# ctrl.net
KiCad netlist of a schematic drawn in EAGLE
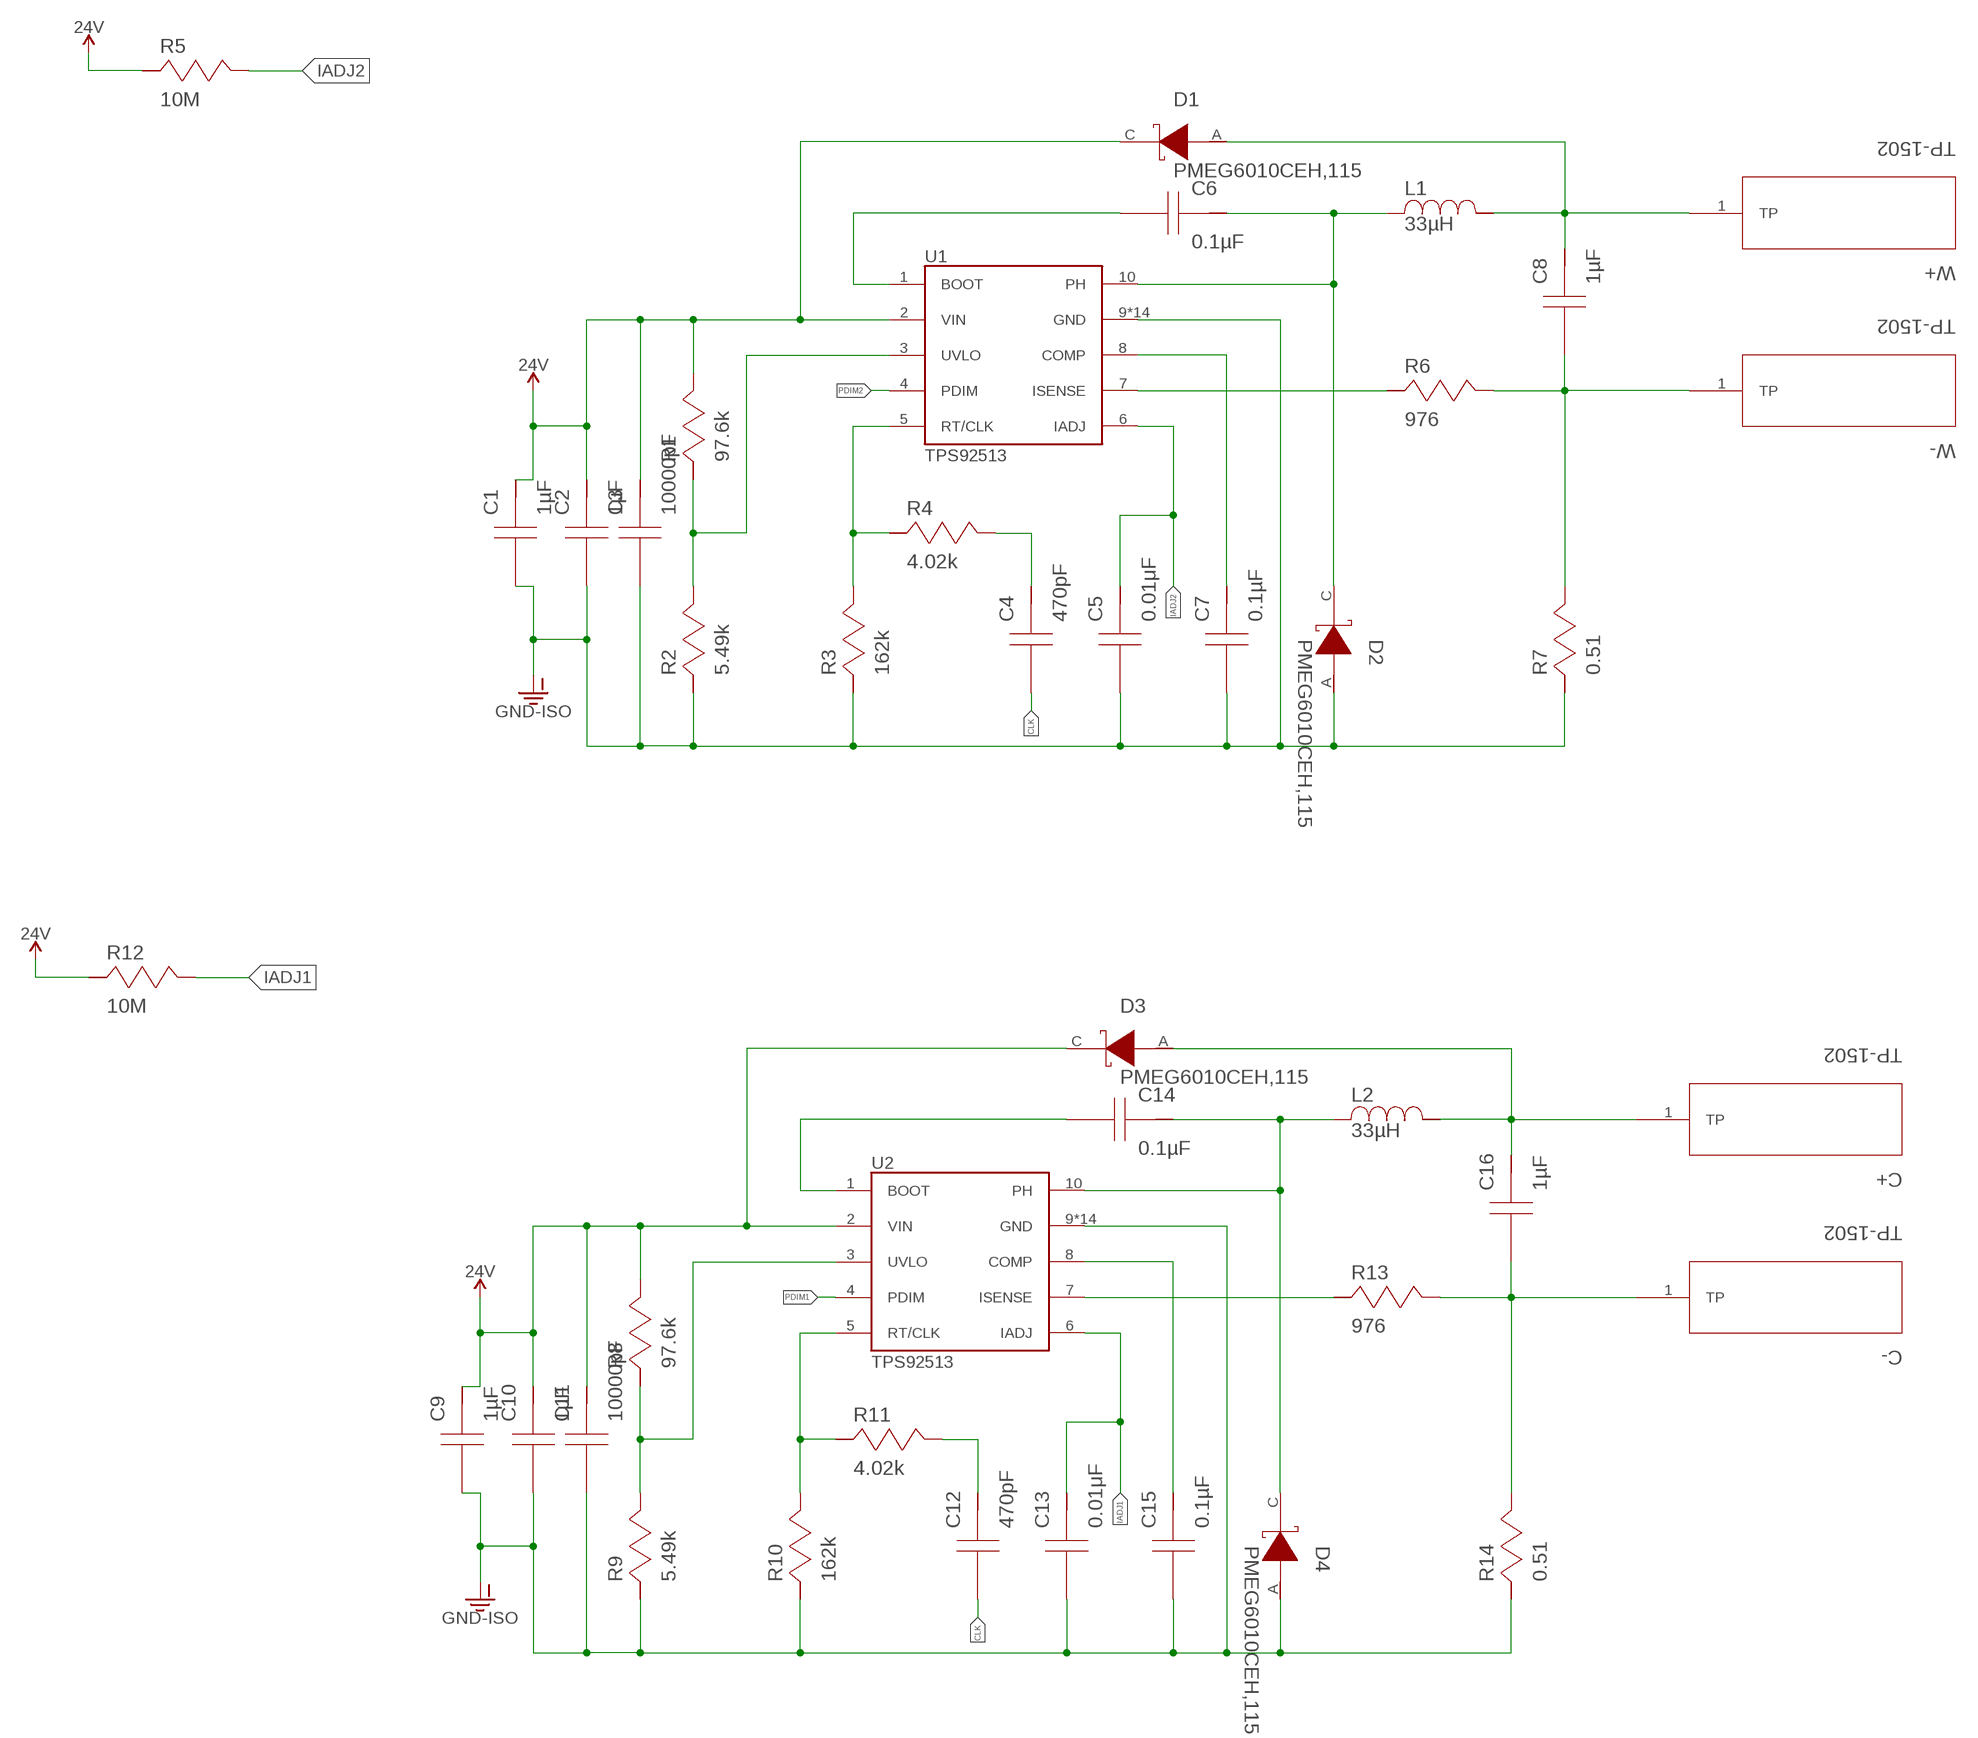
[diagram p0: schematic, sheet 1, part 1 of 2]
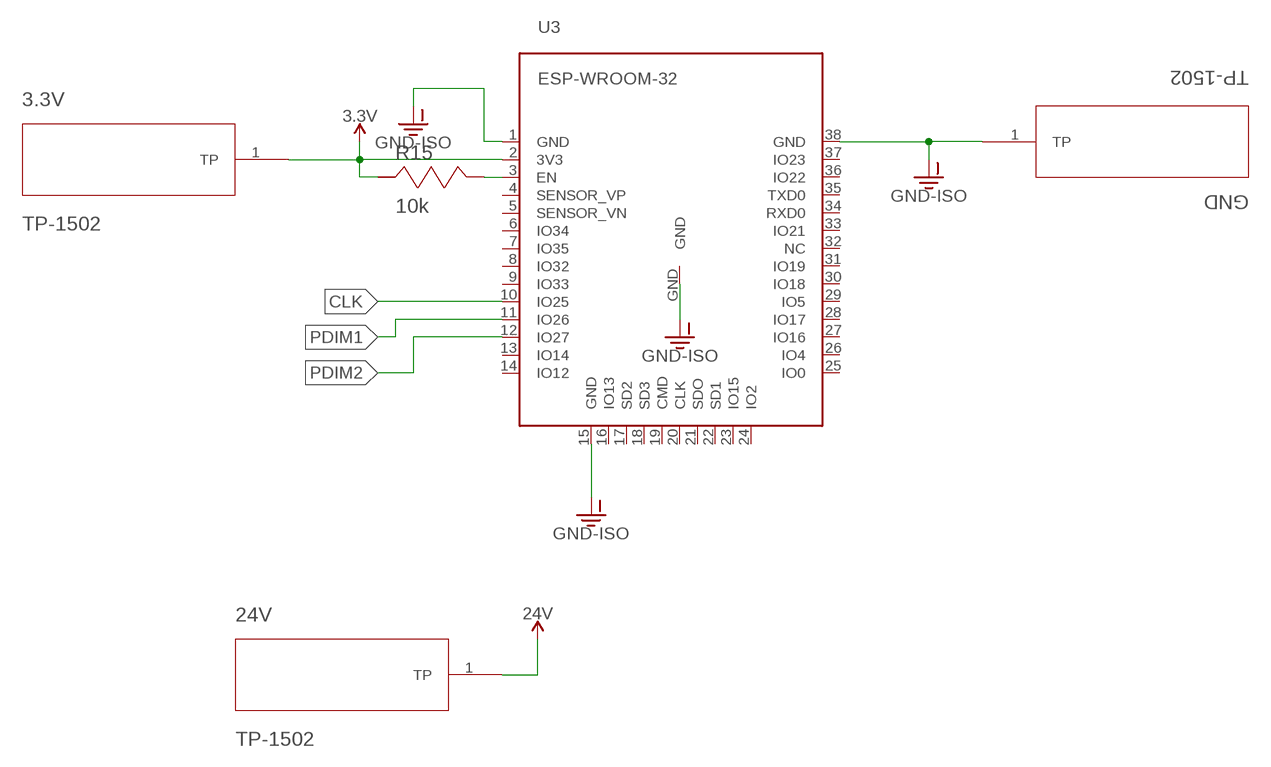
[diagram p1: schematic, sheet 1, part 2 of 2]

(export (version "E")
  (design (tool "Eeschema 10.0.6"))
  (components
    (comp (ref "3.3V")
      (value "TP-1502")
      (footprint "eagle-import:TP-1502")
      (libsource (lib "eagle-import") (part "TP-1502"))
    )
    (comp (ref "24V")
      (value "TP-1502")
      (footprint "eagle-import:TP-1502")
      (libsource (lib "eagle-import") (part "TP-1502"))
    )
    (comp (ref "C+")
      (value "TP-1502")
      (footprint "eagle-import:TP-1502")
      (libsource (lib "eagle-import") (part "TP-1502"))
    )
    (comp (ref "C-")
      (value "TP-1502")
      (footprint "eagle-import:TP-1502")
      (libsource (lib "eagle-import") (part "TP-1502"))
    )
    (comp (ref "C1")
      (value "1µF")
      (footprint "eagle-import:1206")
      (fields
        (field (name "DIGIKEY_PART_NUMBER") "490-6527-1-ND")
        (field (name "PART_NUMBER") "GRM31MR71H105KA88L")
      )
      (libsource (lib "eagle-import") (part "GRM31MR71H105KA88L"))
    )
    (comp (ref "C2")
      (value "1µF")
      (footprint "eagle-import:1206")
      (fields
        (field (name "DIGIKEY_PART_NUMBER") "490-6527-1-ND")
        (field (name "PART_NUMBER") "GRM31MR71H105KA88L")
      )
      (libsource (lib "eagle-import") (part "GRM31MR71H105KA88L"))
    )
    (comp (ref "C3")
      (value "10000pF")
      (footprint "eagle-import:0402")
      (fields
        (field (name "DIGIKEY_PART_NUMBER") "490-4762-1-ND ")
        (field (name "PART_NUMBER") "GCM155R71H103KA55D")
      )
      (libsource (lib "eagle-import") (part "GCM155R71H103KA55D"))
    )
    (comp (ref "C4")
      (value "470pF")
      (footprint "eagle-import:0603")
      (fields
        (field (name "DIGIKEY_PART_NUMBER") "399-5338-1-ND")
        (field (name "MANUFACTURER") "KEMET")
        (field (name "PART_NUMBER") "C0603X471K5RACTU")
      )
      (libsource (lib "eagle-import") (part "C0603X471K5RACTU"))
    )
    (comp (ref "C5")
      (value "0.01μF")
      (footprint "eagle-import:0805")
      (fields
        (field (name "DIGIKEY_PART_NUMBER") "311-1136-1-ND")
        (field (name "PART_NUMBER") "CC0805KRX7R9BB103")
      )
      (libsource (lib "eagle-import") (part "CC0805KRX7R9BB103"))
    )
    (comp (ref "C6")
      (value "0.1µF")
      (footprint "eagle-import:0603")
      (fields
        (field (name "DIGIKEY_PART_NUMBER") "490-1524-1-ND")
        (field (name "MANUFACTURER") "Murata Electronics North America")
        (field (name "PART_NUMBER") "GRM188R71E104KA01D")
      )
      (libsource (lib "eagle-import") (part "GRM188R71E104KA01D"))
    )
    (comp (ref "C7")
      (value "0.1µF")
      (footprint "eagle-import:0805")
      (fields
        (field (name "DIGIKEY_PART_NUMBER") "311-1141-1-ND")
        (field (name "PART_NUMBER") "CC0805KRX7R8BB104")
      )
      (libsource (lib "eagle-import") (part "CC0805KRX7R8BB104"))
    )
    (comp (ref "C8")
      (value "1µF")
      (footprint "eagle-import:0805")
      (fields
        (field (name "DIGIKEY_PART_NUMBER") "587-1438-1-ND")
        (field (name "PART_NUMBER") "GMK212B7105KG-T")
      )
      (libsource (lib "eagle-import") (part "GMK212B7105KG-T"))
    )
    (comp (ref "C9")
      (value "1µF")
      (footprint "eagle-import:1206")
      (fields
        (field (name "DIGIKEY_PART_NUMBER") "490-6527-1-ND")
        (field (name "PART_NUMBER") "GRM31MR71H105KA88L")
      )
      (libsource (lib "eagle-import") (part "GRM31MR71H105KA88L"))
    )
    (comp (ref "C10")
      (value "1µF")
      (footprint "eagle-import:1206")
      (fields
        (field (name "DIGIKEY_PART_NUMBER") "490-6527-1-ND")
        (field (name "PART_NUMBER") "GRM31MR71H105KA88L")
      )
      (libsource (lib "eagle-import") (part "GRM31MR71H105KA88L"))
    )
    (comp (ref "C11")
      (value "10000pF")
      (footprint "eagle-import:0402")
      (fields
        (field (name "DIGIKEY_PART_NUMBER") "490-4762-1-ND ")
        (field (name "PART_NUMBER") "GCM155R71H103KA55D")
      )
      (libsource (lib "eagle-import") (part "GCM155R71H103KA55D"))
    )
    (comp (ref "C12")
      (value "470pF")
      (footprint "eagle-import:0603")
      (fields
        (field (name "DIGIKEY_PART_NUMBER") "399-5338-1-ND")
        (field (name "MANUFACTURER") "KEMET")
        (field (name "PART_NUMBER") "C0603X471K5RACTU")
      )
      (libsource (lib "eagle-import") (part "C0603X471K5RACTU"))
    )
    (comp (ref "C13")
      (value "0.01μF")
      (footprint "eagle-import:0805")
      (fields
        (field (name "DIGIKEY_PART_NUMBER") "311-1136-1-ND")
        (field (name "PART_NUMBER") "CC0805KRX7R9BB103")
      )
      (libsource (lib "eagle-import") (part "CC0805KRX7R9BB103"))
    )
    (comp (ref "C14")
      (value "0.1µF")
      (footprint "eagle-import:0603")
      (fields
        (field (name "DIGIKEY_PART_NUMBER") "490-1524-1-ND")
        (field (name "MANUFACTURER") "Murata Electronics North America")
        (field (name "PART_NUMBER") "GRM188R71E104KA01D")
      )
      (libsource (lib "eagle-import") (part "GRM188R71E104KA01D"))
    )
    (comp (ref "C15")
      (value "0.1µF")
      (footprint "eagle-import:0805")
      (fields
        (field (name "DIGIKEY_PART_NUMBER") "311-1141-1-ND")
        (field (name "PART_NUMBER") "CC0805KRX7R8BB104")
      )
      (libsource (lib "eagle-import") (part "CC0805KRX7R8BB104"))
    )
    (comp (ref "C16")
      (value "1µF")
      (footprint "eagle-import:0805")
      (fields
        (field (name "DIGIKEY_PART_NUMBER") "587-1438-1-ND")
        (field (name "PART_NUMBER") "GMK212B7105KG-T")
      )
      (libsource (lib "eagle-import") (part "GMK212B7105KG-T"))
    )
    (comp (ref "D1")
      (value "PMEG6010CEH,115")
      (footprint "eagle-import:SOD-123F")
      (fields (field (name "DIGIKEY_PART_NUMBER") "1727-3848-1-ND"))
      (libsource (lib "eagle-import") (part "PMEG6010CEH,115"))
    )
    (comp (ref "D2")
      (value "PMEG6010CEH,115")
      (footprint "eagle-import:SOD-123F")
      (fields (field (name "DIGIKEY_PART_NUMBER") "1727-3848-1-ND"))
      (libsource (lib "eagle-import") (part "PMEG6010CEH,115"))
    )
    (comp (ref "D3")
      (value "PMEG6010CEH,115")
      (footprint "eagle-import:SOD-123F")
      (fields (field (name "DIGIKEY_PART_NUMBER") "1727-3848-1-ND"))
      (libsource (lib "eagle-import") (part "PMEG6010CEH,115"))
    )
    (comp (ref "D4")
      (value "PMEG6010CEH,115")
      (footprint "eagle-import:SOD-123F")
      (fields (field (name "DIGIKEY_PART_NUMBER") "1727-3848-1-ND"))
      (libsource (lib "eagle-import") (part "PMEG6010CEH,115"))
    )
    (comp (ref "GND")
      (value "TP-1502")
      (footprint "eagle-import:TP-1502")
      (libsource (lib "eagle-import") (part "TP-1502"))
    )
    (comp (ref "L1")
      (value "33µH")
      (footprint "eagle-import:SRN6045")
      (fields
        (field (name "DIGIKEY_PART_NUMBER") "SRN6045-330MCT-ND")
        (field (name "PART_NUMBER") "SRN6045-330M")
      )
      (libsource (lib "eagle-import") (part "SRN6045-330M"))
    )
    (comp (ref "L2")
      (value "33µH")
      (footprint "eagle-import:SRN6045")
      (fields
        (field (name "DIGIKEY_PART_NUMBER") "SRN6045-330MCT-ND")
        (field (name "PART_NUMBER") "SRN6045-330M")
      )
      (libsource (lib "eagle-import") (part "SRN6045-330M"))
    )
    (comp (ref "R1")
      (value "97.6k")
      (footprint "eagle-import:0402")
      (fields
        (field (name "DIGIKEY_PART_NUMBER") "541-97.6KLCT-ND")
        (field (name "PART_NUMBER") "CRCW040297K6FKED")
      )
      (libsource (lib "eagle-import") (part "CRCW040297K6FKED"))
    )
    (comp (ref "R2")
      (value "5.49k")
      (footprint "eagle-import:0402")
      (fields
        (field (name "DIGIKEY_PART_NUMBER") "541-5.49KLCT-ND")
        (field (name "PART_NUMBER") "CRCW04025K49FKED")
      )
      (libsource (lib "eagle-import") (part "CRCW04025K49FKED"))
    )
    (comp (ref "R3")
      (value "162k")
      (footprint "eagle-import:0402")
      (fields
        (field (name "DIGIKEY_PART_NUMBER") "541-162KLCT-ND")
        (field (name "PART_NUMBER") "CRCW0402162KFKED")
      )
      (libsource (lib "eagle-import") (part "CRCW0402162KFKED"))
    )
    (comp (ref "R4")
      (value "4.02k")
      (footprint "eagle-import:0603")
      (fields
        (field (name "DIGIKEY_PART_NUMBER") "541-4.02KHCT-ND")
        (field (name "MANUFACTURER") "Vishay Dale")
        (field (name "PART_NUMBER") "CRCW06034K02FKEA")
      )
      (libsource (lib "eagle-import") (part "CRCW06034K02FKEA"))
    )
    (comp (ref "R5")
      (value "10M")
      (footprint "eagle-import:0402")
      (fields
        (field (name "DIGIKEY_PART_NUMBER") "541-10MJCT-ND")
        (field (name "MANUFACTURER") "Vishay Dale")
        (field (name "PART_NUMBER") "CRCW040210M0JNED")
      )
      (libsource (lib "eagle-import") (part "CRCW040210M0JNED"))
    )
    (comp (ref "R6")
      (value "976")
      (footprint "eagle-import:0402")
      (fields
        (field (name "DIGIKEY_PART_NUMBER") "541-976LCT-ND")
        (field (name "PART_NUMBER") "CRCW0402976RFKED")
      )
      (libsource (lib "eagle-import") (part "CRCW0402976RFKED"))
    )
    (comp (ref "R7")
      (value "0.51")
      (footprint "eagle-import:0805")
      (fields
        (field (name "DIGIKEY_PART_NUMBER") "CRM0805-FX-R510ELFCT-ND")
        (field (name "PART_NUMBER") "CRM0805-FX-R510ELF")
      )
      (libsource (lib "eagle-import") (part "CRM0805-FX-R510ELF"))
    )
    (comp (ref "R8")
      (value "97.6k")
      (footprint "eagle-import:0402")
      (fields
        (field (name "DIGIKEY_PART_NUMBER") "541-97.6KLCT-ND")
        (field (name "PART_NUMBER") "CRCW040297K6FKED")
      )
      (libsource (lib "eagle-import") (part "CRCW040297K6FKED"))
    )
    (comp (ref "R9")
      (value "5.49k")
      (footprint "eagle-import:0402")
      (fields
        (field (name "DIGIKEY_PART_NUMBER") "541-5.49KLCT-ND")
        (field (name "PART_NUMBER") "CRCW04025K49FKED")
      )
      (libsource (lib "eagle-import") (part "CRCW04025K49FKED"))
    )
    (comp (ref "R10")
      (value "162k")
      (footprint "eagle-import:0402")
      (fields
        (field (name "DIGIKEY_PART_NUMBER") "541-162KLCT-ND")
        (field (name "PART_NUMBER") "CRCW0402162KFKED")
      )
      (libsource (lib "eagle-import") (part "CRCW0402162KFKED"))
    )
    (comp (ref "R11")
      (value "4.02k")
      (footprint "eagle-import:0603")
      (fields
        (field (name "DIGIKEY_PART_NUMBER") "541-4.02KHCT-ND")
        (field (name "MANUFACTURER") "Vishay Dale")
        (field (name "PART_NUMBER") "CRCW06034K02FKEA")
      )
      (libsource (lib "eagle-import") (part "CRCW06034K02FKEA"))
    )
    (comp (ref "R12")
      (value "10M")
      (footprint "eagle-import:0402")
      (fields
        (field (name "DIGIKEY_PART_NUMBER") "541-10MJCT-ND")
        (field (name "MANUFACTURER") "Vishay Dale")
        (field (name "PART_NUMBER") "CRCW040210M0JNED")
      )
      (libsource (lib "eagle-import") (part "CRCW040210M0JNED"))
    )
    (comp (ref "R13")
      (value "976")
      (footprint "eagle-import:0402")
      (fields
        (field (name "DIGIKEY_PART_NUMBER") "541-976LCT-ND")
        (field (name "PART_NUMBER") "CRCW0402976RFKED")
      )
      (libsource (lib "eagle-import") (part "CRCW0402976RFKED"))
    )
    (comp (ref "R14")
      (value "0.51")
      (footprint "eagle-import:0805")
      (fields
        (field (name "DIGIKEY_PART_NUMBER") "CRM0805-FX-R510ELFCT-ND")
        (field (name "PART_NUMBER") "CRM0805-FX-R510ELF")
      )
      (libsource (lib "eagle-import") (part "CRM0805-FX-R510ELF"))
    )
    (comp (ref "R15")
      (value "10k")
      (footprint "eagle-import:0603")
      (fields
        (field (name "DIGIKEY_PART_NUMBER") "541-10.0KHCT-ND")
        (field (name "MANUFACTURER") "Vishay Dale")
        (field (name "PART_NUMBER") "CRCW060310K0FKEA")
      )
      (libsource (lib "eagle-import") (part "CRCW060310K0FKEA"))
    )
    (comp (ref "U1")
      (value "TPS92513")
      (footprint "eagle-import:TPS92513")
      (fields
        (field (name "DIGIKEY_PART_NUMBER") "296-42113-1-ND")
        (field (name "PART_NUMBER") "TPS92513DGQT")
      )
      (libsource (lib "eagle-import") (part "TPS92513"))
    )
    (comp (ref "U2")
      (value "TPS92513")
      (footprint "eagle-import:TPS92513")
      (fields
        (field (name "DIGIKEY_PART_NUMBER") "296-42113-1-ND")
        (field (name "PART_NUMBER") "TPS92513DGQT")
      )
      (libsource (lib "eagle-import") (part "TPS92513"))
    )
    (comp (ref "U3")
      (value "ESP-WROOM-32")
      (footprint "eagle-import:ESP-WROOM-32")
      (libsource (lib "eagle-import") (part "ESP-WROOM-32"))
    )
    (comp (ref "W+")
      (value "TP-1502")
      (footprint "eagle-import:TP-1502")
      (libsource (lib "eagle-import") (part "TP-1502"))
    )
    (comp (ref "W-")
      (value "TP-1502")
      (footprint "eagle-import:TP-1502")
      (libsource (lib "eagle-import") (part "TP-1502"))
    )
  )
  (nets
    (net (code "1") (name "3.3V") (class "Default")
      (node (ref "3.3V") (pin "1") (pinfunction "TP_1") (pintype "passive"))
      (node (ref "R15") (pin "2") (pinfunction "2_2") (pintype "passive"))
      (node (ref "U3") (pin "2") (pinfunction "3V3_2") (pintype "bidirectional"))
    )
    (net (code "2") (name "24V") (class "Default")
      (node (ref "24V") (pin "1") (pinfunction "TP_1") (pintype "passive"))
      (node (ref "C1") (pin "1") (pinfunction "1_1") (pintype "passive"))
      (node (ref "C10") (pin "1") (pinfunction "1_1") (pintype "passive"))
      (node (ref "C11") (pin "1") (pinfunction "1_1") (pintype "passive"))
      (node (ref "C2") (pin "1") (pinfunction "1_1") (pintype "passive"))
      (node (ref "C3") (pin "1") (pinfunction "1_1") (pintype "passive"))
      (node (ref "C9") (pin "1") (pinfunction "1_1") (pintype "passive"))
      (node (ref "D1") (pin "C") (pinfunction "C_C") (pintype "passive"))
      (node (ref "D3") (pin "C") (pinfunction "C_C") (pintype "passive"))
      (node (ref "R1") (pin "1") (pinfunction "1_1") (pintype "passive"))
      (node (ref "R12") (pin "2") (pinfunction "2_2") (pintype "passive"))
      (node (ref "R5") (pin "2") (pinfunction "2_2") (pintype "passive"))
      (node (ref "R8") (pin "1") (pinfunction "1_1") (pintype "passive"))
      (node (ref "U1") (pin "2") (pinfunction "VIN_2") (pintype "power_in"))
      (node (ref "U2") (pin "2") (pinfunction "VIN_2") (pintype "power_in"))
    )
    (net (code "3") (name "CLK") (class "Default")
      (node (ref "C12") (pin "2") (pinfunction "2_2") (pintype "passive"))
      (node (ref "C4") (pin "2") (pinfunction "2_2") (pintype "passive"))
      (node (ref "U3") (pin "10") (pinfunction "IO25_10") (pintype "bidirectional"))
    )
    (net (code "4") (name "GND-ISO") (class "Default")
      (node (ref "C1") (pin "2") (pinfunction "2_2") (pintype "passive"))
      (node (ref "C10") (pin "2") (pinfunction "2_2") (pintype "passive"))
      (node (ref "C11") (pin "2") (pinfunction "2_2") (pintype "passive"))
      (node (ref "C13") (pin "2") (pinfunction "2_2") (pintype "passive"))
      (node (ref "C15") (pin "2") (pinfunction "2_2") (pintype "passive"))
      (node (ref "C2") (pin "2") (pinfunction "2_2") (pintype "passive"))
      (node (ref "C3") (pin "2") (pinfunction "2_2") (pintype "passive"))
      (node (ref "C5") (pin "2") (pinfunction "2_2") (pintype "passive"))
      (node (ref "C7") (pin "2") (pinfunction "2_2") (pintype "passive"))
      (node (ref "C9") (pin "2") (pinfunction "2_2") (pintype "passive"))
      (node (ref "D2") (pin "A") (pinfunction "A_A") (pintype "passive"))
      (node (ref "D4") (pin "A") (pinfunction "A_A") (pintype "passive"))
      (node (ref "GND") (pin "1") (pinfunction "TP_1") (pintype "passive"))
      (node (ref "R10") (pin "2") (pinfunction "2_2") (pintype "passive"))
      (node (ref "R14") (pin "2") (pinfunction "2_2") (pintype "passive"))
      (node (ref "R2") (pin "2") (pinfunction "2_2") (pintype "passive"))
      (node (ref "R3") (pin "2") (pinfunction "2_2") (pintype "passive"))
      (node (ref "R7") (pin "2") (pinfunction "2_2") (pintype "passive"))
      (node (ref "R9") (pin "2") (pinfunction "2_2") (pintype "passive"))
      (node (ref "U1") (pin "9") (pinfunction "GND_9") (pintype "power_in"))
      (node (ref "U1") (pin "GND-ISO") (pinfunction "GND_GND-ISO") (pintype "power_in"))
      (node (ref "U1") (pin "P$1") (pinfunction "GND_P$1") (pintype "power_in"))
      (node (ref "U1") (pin "P$10") (pinfunction "GND_P$10") (pintype "power_in"))
      (node (ref "U1") (pin "P$11") (pinfunction "GND_P$11") (pintype "power_in"))
      (node (ref "U1") (pin "P$12") (pinfunction "GND_P$12") (pintype "power_in"))
      (node (ref "U1") (pin "P$2") (pinfunction "GND_P$2") (pintype "power_in"))
      (node (ref "U1") (pin "P$3") (pinfunction "GND_P$3") (pintype "power_in"))
      (node (ref "U1") (pin "P$4") (pinfunction "GND_P$4") (pintype "power_in"))
      (node (ref "U1") (pin "P$5") (pinfunction "GND_P$5") (pintype "power_in"))
      (node (ref "U1") (pin "P$6") (pinfunction "GND_P$6") (pintype "power_in"))
      (node (ref "U1") (pin "P$7") (pinfunction "GND_P$7") (pintype "power_in"))
      (node (ref "U1") (pin "P$8") (pinfunction "GND_P$8") (pintype "power_in"))
      (node (ref "U1") (pin "P$9") (pinfunction "GND_P$9") (pintype "power_in"))
      (node (ref "U2") (pin "9") (pinfunction "GND_9") (pintype "power_in"))
      (node (ref "U2") (pin "GND-ISO") (pinfunction "GND_GND-ISO") (pintype "power_in"))
      (node (ref "U2") (pin "P$1") (pinfunction "GND_P$1") (pintype "power_in"))
      (node (ref "U2") (pin "P$10") (pinfunction "GND_P$10") (pintype "power_in"))
      (node (ref "U2") (pin "P$11") (pinfunction "GND_P$11") (pintype "power_in"))
      (node (ref "U2") (pin "P$12") (pinfunction "GND_P$12") (pintype "power_in"))
      (node (ref "U2") (pin "P$2") (pinfunction "GND_P$2") (pintype "power_in"))
      (node (ref "U2") (pin "P$3") (pinfunction "GND_P$3") (pintype "power_in"))
      (node (ref "U2") (pin "P$4") (pinfunction "GND_P$4") (pintype "power_in"))
      (node (ref "U2") (pin "P$5") (pinfunction "GND_P$5") (pintype "power_in"))
      (node (ref "U2") (pin "P$6") (pinfunction "GND_P$6") (pintype "power_in"))
      (node (ref "U2") (pin "P$7") (pinfunction "GND_P$7") (pintype "power_in"))
      (node (ref "U2") (pin "P$8") (pinfunction "GND_P$8") (pintype "power_in"))
      (node (ref "U2") (pin "P$9") (pinfunction "GND_P$9") (pintype "power_in"))
      (node (ref "U3") (pin "1") (pinfunction "GND_1") (pintype "bidirectional"))
      (node (ref "U3") (pin "15") (pinfunction "GND_15") (pintype "bidirectional"))
      (node (ref "U3") (pin "38") (pinfunction "GND_38") (pintype "bidirectional"))
      (node (ref "U3") (pin "GND") (pinfunction "GND_GND") (pintype "bidirectional"))
    )
    (net (code "5") (name "IADJ1") (class "Default")
      (node (ref "C13") (pin "1") (pinfunction "1_1") (pintype "passive"))
      (node (ref "R12") (pin "1") (pinfunction "1_1") (pintype "passive"))
      (node (ref "U2") (pin "6") (pinfunction "IADJ_6") (pintype "input"))
    )
    (net (code "6") (name "IADJ2") (class "Default")
      (node (ref "C5") (pin "1") (pinfunction "1_1") (pintype "passive"))
      (node (ref "R5") (pin "1") (pinfunction "1_1") (pintype "passive"))
      (node (ref "U1") (pin "6") (pinfunction "IADJ_6") (pintype "input"))
    )
    (net (code "7") (name "Net-(C+-TP)") (class "Default")
      (node (ref "C+") (pin "1") (pinfunction "TP_1") (pintype "passive"))
      (node (ref "C16") (pin "1") (pinfunction "1_1") (pintype "passive"))
      (node (ref "D3") (pin "A") (pinfunction "A_A") (pintype "passive"))
      (node (ref "L2") (pin "2") (pinfunction "2_2") (pintype "passive"))
    )
    (net (code "8") (name "Net-(C--TP)") (class "Default")
      (node (ref "C-") (pin "1") (pinfunction "TP_1") (pintype "passive"))
      (node (ref "C16") (pin "2") (pinfunction "2_2") (pintype "passive"))
      (node (ref "R13") (pin "1") (pinfunction "1_1") (pintype "passive"))
      (node (ref "R14") (pin "1") (pinfunction "1_1") (pintype "passive"))
    )
    (net (code "9") (name "Net-(C4-Pad1)") (class "Default")
      (node (ref "C4") (pin "1") (pinfunction "1_1") (pintype "passive"))
      (node (ref "R4") (pin "1") (pinfunction "1_1") (pintype "passive"))
    )
    (net (code "10") (name "Net-(C12-Pad1)") (class "Default")
      (node (ref "C12") (pin "1") (pinfunction "1_1") (pintype "passive"))
      (node (ref "R11") (pin "1") (pinfunction "1_1") (pintype "passive"))
    )
    (net (code "11") (name "Net-(U1-BOOT)") (class "Default")
      (node (ref "C6") (pin "2") (pinfunction "2_2") (pintype "passive"))
      (node (ref "U1") (pin "1") (pinfunction "BOOT_1") (pintype "output"))
    )
    (net (code "12") (name "Net-(U1-COMP)") (class "Default")
      (node (ref "C7") (pin "1") (pinfunction "1_1") (pintype "passive"))
      (node (ref "U1") (pin "8") (pinfunction "COMP_8") (pintype "output"))
    )
    (net (code "13") (name "Net-(U1-ISENSE)") (class "Default")
      (node (ref "R6") (pin "2") (pinfunction "2_2") (pintype "passive"))
      (node (ref "U1") (pin "7") (pinfunction "ISENSE_7") (pintype "input"))
    )
    (net (code "14") (name "Net-(U1-PH)") (class "Default")
      (node (ref "C6") (pin "1") (pinfunction "1_1") (pintype "passive"))
      (node (ref "D2") (pin "C") (pinfunction "C_C") (pintype "passive"))
      (node (ref "L1") (pin "1") (pinfunction "1_1") (pintype "passive"))
      (node (ref "U1") (pin "10") (pinfunction "PH_10") (pintype "output"))
    )
    (net (code "15") (name "Net-(U1-RT{slash}CLK)") (class "Default")
      (node (ref "R3") (pin "1") (pinfunction "1_1") (pintype "passive"))
      (node (ref "R4") (pin "2") (pinfunction "2_2") (pintype "passive"))
      (node (ref "U1") (pin "5") (pinfunction "RT/CLK_5") (pintype "input"))
    )
    (net (code "16") (name "Net-(U1-UVLO)") (class "Default")
      (node (ref "R1") (pin "2") (pinfunction "2_2") (pintype "passive"))
      (node (ref "R2") (pin "1") (pinfunction "1_1") (pintype "passive"))
      (node (ref "U1") (pin "3") (pinfunction "UVLO_3") (pintype "input"))
    )
    (net (code "17") (name "Net-(U2-BOOT)") (class "Default")
      (node (ref "C14") (pin "2") (pinfunction "2_2") (pintype "passive"))
      (node (ref "U2") (pin "1") (pinfunction "BOOT_1") (pintype "output"))
    )
    (net (code "18") (name "Net-(U2-COMP)") (class "Default")
      (node (ref "C15") (pin "1") (pinfunction "1_1") (pintype "passive"))
      (node (ref "U2") (pin "8") (pinfunction "COMP_8") (pintype "output"))
    )
    (net (code "19") (name "Net-(U2-ISENSE)") (class "Default")
      (node (ref "R13") (pin "2") (pinfunction "2_2") (pintype "passive"))
      (node (ref "U2") (pin "7") (pinfunction "ISENSE_7") (pintype "input"))
    )
    (net (code "20") (name "Net-(U2-PH)") (class "Default")
      (node (ref "C14") (pin "1") (pinfunction "1_1") (pintype "passive"))
      (node (ref "D4") (pin "C") (pinfunction "C_C") (pintype "passive"))
      (node (ref "L2") (pin "1") (pinfunction "1_1") (pintype "passive"))
      (node (ref "U2") (pin "10") (pinfunction "PH_10") (pintype "output"))
    )
    (net (code "21") (name "Net-(U2-RT{slash}CLK)") (class "Default")
      (node (ref "R10") (pin "1") (pinfunction "1_1") (pintype "passive"))
      (node (ref "R11") (pin "2") (pinfunction "2_2") (pintype "passive"))
      (node (ref "U2") (pin "5") (pinfunction "RT/CLK_5") (pintype "input"))
    )
    (net (code "22") (name "Net-(U2-UVLO)") (class "Default")
      (node (ref "R8") (pin "2") (pinfunction "2_2") (pintype "passive"))
      (node (ref "R9") (pin "1") (pinfunction "1_1") (pintype "passive"))
      (node (ref "U2") (pin "3") (pinfunction "UVLO_3") (pintype "input"))
    )
    (net (code "23") (name "Net-(U3-EN)") (class "Default")
      (node (ref "R15") (pin "1") (pinfunction "1_1") (pintype "passive"))
      (node (ref "U3") (pin "3") (pinfunction "EN_3") (pintype "bidirectional"))
    )
    (net (code "24") (name "Net-(W+-TP)") (class "Default")
      (node (ref "C8") (pin "1") (pinfunction "1_1") (pintype "passive"))
      (node (ref "D1") (pin "A") (pinfunction "A_A") (pintype "passive"))
      (node (ref "L1") (pin "2") (pinfunction "2_2") (pintype "passive"))
      (node (ref "W+") (pin "1") (pinfunction "TP_1") (pintype "passive"))
    )
    (net (code "25") (name "Net-(W--TP)") (class "Default")
      (node (ref "C8") (pin "2") (pinfunction "2_2") (pintype "passive"))
      (node (ref "R6") (pin "1") (pinfunction "1_1") (pintype "passive"))
      (node (ref "R7") (pin "1") (pinfunction "1_1") (pintype "passive"))
      (node (ref "W-") (pin "1") (pinfunction "TP_1") (pintype "passive"))
    )
    (net (code "26") (name "PDIM1") (class "Default")
      (node (ref "U2") (pin "4") (pinfunction "PDIM_4") (pintype "input"))
      (node (ref "U3") (pin "11") (pinfunction "IO26_11") (pintype "bidirectional"))
    )
    (net (code "27") (name "PDIM2") (class "Default")
      (node (ref "U1") (pin "4") (pinfunction "PDIM_4") (pintype "input"))
      (node (ref "U3") (pin "12") (pinfunction "IO27_12") (pintype "bidirectional"))
    )
    (net (code "28") (name "unconnected-(U3-CLK-Pad20)") (class "Default")
      (node (ref "U3") (pin "20") (pinfunction "CLK_20") (pintype "bidirectional"))
    )
    (net (code "29") (name "unconnected-(U3-CMD-Pad19)") (class "Default")
      (node (ref "U3") (pin "19") (pinfunction "CMD_19") (pintype "bidirectional"))
    )
    (net (code "30") (name "unconnected-(U3-IO0-Pad25)") (class "Default")
      (node (ref "U3") (pin "25") (pinfunction "IO0_25") (pintype "bidirectional"))
    )
    (net (code "31") (name "unconnected-(U3-IO2-Pad24)") (class "Default")
      (node (ref "U3") (pin "24") (pinfunction "IO2_24") (pintype "bidirectional"))
    )
    (net (code "32") (name "unconnected-(U3-IO4-Pad26)") (class "Default")
      (node (ref "U3") (pin "26") (pinfunction "IO4_26") (pintype "bidirectional"))
    )
    (net (code "33") (name "unconnected-(U3-IO5-Pad29)") (class "Default")
      (node (ref "U3") (pin "29") (pinfunction "IO5_29") (pintype "bidirectional"))
    )
    (net (code "34") (name "unconnected-(U3-IO12-Pad14)") (class "Default")
      (node (ref "U3") (pin "14") (pinfunction "IO12_14") (pintype "bidirectional"))
    )
    (net (code "35") (name "unconnected-(U3-IO13-Pad16)") (class "Default")
      (node (ref "U3") (pin "16") (pinfunction "IO13_16") (pintype "bidirectional"))
    )
    (net (code "36") (name "unconnected-(U3-IO14-Pad13)") (class "Default")
      (node (ref "U3") (pin "13") (pinfunction "IO14_13") (pintype "bidirectional"))
    )
    (net (code "37") (name "unconnected-(U3-IO15-Pad23)") (class "Default")
      (node (ref "U3") (pin "23") (pinfunction "IO15_23") (pintype "bidirectional"))
    )
    (net (code "38") (name "unconnected-(U3-IO16-Pad27)") (class "Default")
      (node (ref "U3") (pin "27") (pinfunction "IO16_27") (pintype "bidirectional"))
    )
    (net (code "39") (name "unconnected-(U3-IO17-Pad28)") (class "Default")
      (node (ref "U3") (pin "28") (pinfunction "IO17_28") (pintype "bidirectional"))
    )
    (net (code "40") (name "unconnected-(U3-IO18-Pad30)") (class "Default")
      (node (ref "U3") (pin "30") (pinfunction "IO18_30") (pintype "bidirectional"))
    )
    (net (code "41") (name "unconnected-(U3-IO19-Pad31)") (class "Default")
      (node (ref "U3") (pin "31") (pinfunction "IO19_31") (pintype "bidirectional"))
    )
    (net (code "42") (name "unconnected-(U3-IO21-Pad33)") (class "Default")
      (node (ref "U3") (pin "33") (pinfunction "IO21_33") (pintype "bidirectional"))
    )
    (net (code "43") (name "unconnected-(U3-IO22-Pad36)") (class "Default")
      (node (ref "U3") (pin "36") (pinfunction "IO22_36") (pintype "bidirectional"))
    )
    (net (code "44") (name "unconnected-(U3-IO23-Pad37)") (class "Default")
      (node (ref "U3") (pin "37") (pinfunction "IO23_37") (pintype "bidirectional"))
    )
    (net (code "45") (name "unconnected-(U3-IO32-Pad8)") (class "Default")
      (node (ref "U3") (pin "8") (pinfunction "IO32_8") (pintype "bidirectional"))
    )
    (net (code "46") (name "unconnected-(U3-IO33-Pad9)") (class "Default")
      (node (ref "U3") (pin "9") (pinfunction "IO33_9") (pintype "bidirectional"))
    )
    (net (code "47") (name "unconnected-(U3-IO34-Pad6)") (class "Default")
      (node (ref "U3") (pin "6") (pinfunction "IO34_6") (pintype "bidirectional"))
    )
    (net (code "48") (name "unconnected-(U3-IO35-Pad7)") (class "Default")
      (node (ref "U3") (pin "7") (pinfunction "IO35_7") (pintype "bidirectional"))
    )
    (net (code "49") (name "unconnected-(U3-NC-Pad32)") (class "Default")
      (node (ref "U3") (pin "32") (pinfunction "NC_32") (pintype "bidirectional"))
    )
    (net (code "50") (name "unconnected-(U3-RXD0-Pad34)") (class "Default")
      (node (ref "U3") (pin "34") (pinfunction "RXD0_34") (pintype "bidirectional"))
    )
    (net (code "51") (name "unconnected-(U3-SD1-Pad22)") (class "Default")
      (node (ref "U3") (pin "22") (pinfunction "SD1_22") (pintype "bidirectional"))
    )
    (net (code "52") (name "unconnected-(U3-SD2-Pad17)") (class "Default")
      (node (ref "U3") (pin "17") (pinfunction "SD2_17") (pintype "bidirectional"))
    )
    (net (code "53") (name "unconnected-(U3-SD3-Pad18)") (class "Default")
      (node (ref "U3") (pin "18") (pinfunction "SD3_18") (pintype "bidirectional"))
    )
    (net (code "54") (name "unconnected-(U3-SDO-Pad21)") (class "Default")
      (node (ref "U3") (pin "21") (pinfunction "SDO_21") (pintype "bidirectional"))
    )
    (net (code "55") (name "unconnected-(U3-SENSOR_VN-Pad5)") (class "Default")
      (node (ref "U3") (pin "5") (pinfunction "SENSOR_VN_5") (pintype "bidirectional"))
    )
    (net (code "56") (name "unconnected-(U3-SENSOR_VP-Pad4)") (class "Default")
      (node (ref "U3") (pin "4") (pinfunction "SENSOR_VP_4") (pintype "bidirectional"))
    )
    (net (code "57") (name "unconnected-(U3-TXD0-Pad35)") (class "Default")
      (node (ref "U3") (pin "35") (pinfunction "TXD0_35") (pintype "bidirectional"))
    )
  )
)
